# RoBeast_Current_Sense.net
KiCad netlist of a schematic drawn in Altium Designer
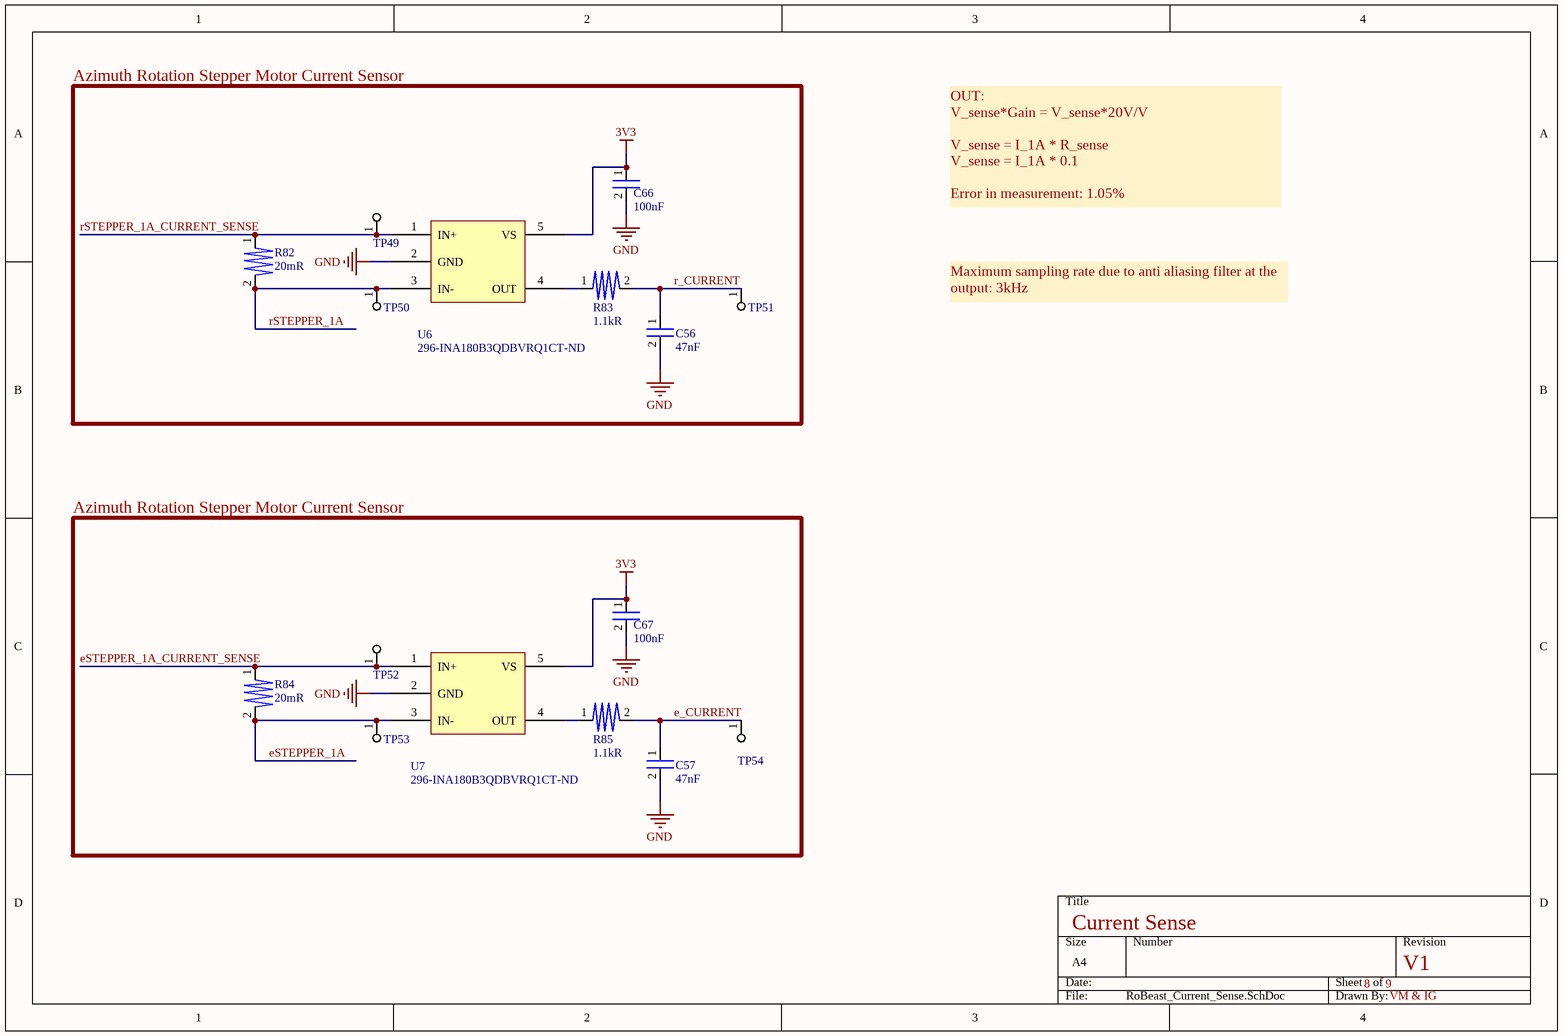
[diagram p0: RoBeast_Current_Sense.SchDoc]

(export (version "E")
  (design (tool "Eeschema 10.0.6"))
  (components
    (comp (ref "C56")
      (value "47nF")
      (footprint "0805")
      (fields
        (field (name "MANUFACTURER") "Samsung")
        (field (name "MANUFACTURER PART NUMBER") "CL21B473KBCNNNC")
      )
      (libsource (lib "RoBeast_Schematic_Library") (part "CL21B473KBCNNNC"))
    )
    (comp (ref "C57")
      (value "47nF")
      (footprint "0805")
      (fields
        (field (name "MANUFACTURER") "Samsung")
        (field (name "MANUFACTURER PART NUMBER") "CL21B473KBCNNNC")
      )
      (libsource (lib "RoBeast_Schematic_Library") (part "CL21B473KBCNNNC"))
    )
    (comp (ref "C66")
      (value "100nF")
      (footprint "0805")
      (fields
        (field (name "MANUFACTURER") "KEMET")
        (field (name "MANUFACTURER PART NUMBER") "C0805C104J5RACTU")
      )
      (libsource (lib "RoBeast_Schematic_Library") (part "C0805C104J5RAC7800"))
    )
    (comp (ref "C67")
      (value "100nF")
      (footprint "0805")
      (fields
        (field (name "MANUFACTURER") "KEMET")
        (field (name "MANUFACTURER PART NUMBER") "C0805C104J5RACTU")
      )
      (libsource (lib "RoBeast_Schematic_Library") (part "C0805C104J5RAC7800"))
    )
    (comp (ref "R82")
      (value "20mR")
      (footprint "0805")
      (description "Resistor Thick Film 0.02Ohm 0.5% 0.5W 2-Pin 0805 T/R")
      (fields
        (field (name "MANUFACTURER") "Panasonic")
        (field (name "MANUFACTURER PART NUMBER") "ERJ-6CWDR020V")
      )
      (libsource (lib "RoBeast_Schematic_Library") (part "ERJ-6CWDR020V"))
    )
    (comp (ref "R83")
      (value "1.1kR")
      (footprint "0805")
      (fields
        (field (name "MANUFACTURER") "Vishay Dale")
        (field (name "MANUFACTURER PART NUMBER") "RCS08051K10FKEA")
      )
      (libsource (lib "RoBeast_Schematic_Library") (part "RCS08051K10FKEA"))
    )
    (comp (ref "R84")
      (value "20mR")
      (footprint "0805")
      (description "Resistor Thick Film 0.02Ohm 0.5% 0.5W 2-Pin 0805 T/R")
      (fields
        (field (name "MANUFACTURER") "Panasonic")
        (field (name "MANUFACTURER PART NUMBER") "ERJ-6CWDR020V")
      )
      (libsource (lib "RoBeast_Schematic_Library") (part "ERJ-6CWDR020V"))
    )
    (comp (ref "R85")
      (value "1.1kR")
      (footprint "0805")
      (fields
        (field (name "MANUFACTURER") "Vishay Dale")
        (field (name "MANUFACTURER PART NUMBER") "RCS08051K10FKEA")
      )
      (libsource (lib "RoBeast_Schematic_Library") (part "RCS08051K10FKEA"))
    )
    (comp (ref "TP49")
      (value "Test Point")
      (footprint "RCWCTE")
      (description "Testing/Accessories")
      (fields (field (name "MANUFACTURER") "KOA Speer") (field (name "MANUFACTURER PART NUMBER") "RCWCTE"))
      (libsource (lib "RoBeast_Schematic_Library") (part "RCWCTE"))
    )
    (comp (ref "TP50")
      (value "Test Point")
      (footprint "RCWCTE")
      (description "Testing/Accessories")
      (fields (field (name "MANUFACTURER") "KOA Speer") (field (name "MANUFACTURER PART NUMBER") "RCWCTE"))
      (libsource (lib "RoBeast_Schematic_Library") (part "RCWCTE"))
    )
    (comp (ref "TP51")
      (value "Test Point")
      (footprint "RCWCTE")
      (description "Testing/Accessories")
      (fields (field (name "MANUFACTURER") "KOA Speer") (field (name "MANUFACTURER PART NUMBER") "RCWCTE"))
      (libsource (lib "RoBeast_Schematic_Library") (part "RCWCTE"))
    )
    (comp (ref "TP52")
      (value "Test Point")
      (footprint "RCWCTE")
      (description "Testing/Accessories")
      (fields (field (name "MANUFACTURER") "KOA Speer") (field (name "MANUFACTURER PART NUMBER") "RCWCTE"))
      (libsource (lib "RoBeast_Schematic_Library") (part "RCWCTE"))
    )
    (comp (ref "TP53")
      (value "Test Point")
      (footprint "RCWCTE")
      (description "Testing/Accessories")
      (fields (field (name "MANUFACTURER") "KOA Speer") (field (name "MANUFACTURER PART NUMBER") "RCWCTE"))
      (libsource (lib "RoBeast_Schematic_Library") (part "RCWCTE"))
    )
    (comp (ref "TP54")
      (value "Test Point")
      (footprint "RCWCTE")
      (description "Testing/Accessories")
      (fields (field (name "MANUFACTURER") "KOA Speer") (field (name "MANUFACTURER PART NUMBER") "RCWCTE"))
      (libsource (lib "RoBeast_Schematic_Library") (part "RCWCTE"))
    )
    (comp (ref "U6")
      (value "Current Sensor, Gain 100V/V")
      (footprint "INA180B3QDBVRQ1")
      (description "Operational Amplifier, 1 Func, 500uV Offset-Max, PDSO5")
      (fields
        (field (name "MANUFACTURER") "Texas Instruments")
        (field (name "MANUFACTURER PART NUMBER") "INA180B3QDBVRQ1")
        (field (name "SUPPLIER PART NUMBER 1") "296-INA180B3QDBVRQ1CT-ND")
      )
      (libsource (lib "RoBeast_Schematic_Library") (part "INA180B3QDBVRQ1"))
    )
    (comp (ref "U7")
      (value "Current Sensor, Gain 100V/V")
      (footprint "INA180B3QDBVRQ1")
      (description "Operational Amplifier, 1 Func, 500uV Offset-Max, PDSO5")
      (fields
        (field (name "MANUFACTURER") "Texas Instruments")
        (field (name "MANUFACTURER PART NUMBER") "INA180B3QDBVRQ1")
        (field (name "SUPPLIER PART NUMBER 1") "296-INA180B3QDBVRQ1CT-ND")
      )
      (libsource (lib "RoBeast_Schematic_Library") (part "INA180B3QDBVRQ1"))
    )
  )
  (nets
    (net (code "1") (name "/eSTEPPER_1A") (class "Default")
      (node (ref "R84") (pin "2") (pinfunction "2_2") (pintype "passive"))
      (node (ref "TP53") (pin "1") (pinfunction "1_1") (pintype "passive"))
      (node (ref "U7") (pin "3") (pinfunction "IN-_3") (pintype "passive"))
    )
    (net (code "2") (name "/eSTEPPER_1A_CURRENT_SENSE") (class "Default")
      (node (ref "R84") (pin "1") (pinfunction "1_1") (pintype "passive"))
      (node (ref "TP52") (pin "1") (pinfunction "1_1") (pintype "passive"))
      (node (ref "U7") (pin "1") (pinfunction "IN+_1") (pintype "passive"))
    )
    (net (code "3") (name "/e_CURRENT") (class "Default")
      (node (ref "C57") (pin "1") (pinfunction "1_1") (pintype "passive"))
      (node (ref "R85") (pin "2") (pinfunction "2_2") (pintype "passive"))
      (node (ref "TP54") (pin "1") (pinfunction "1_1") (pintype "passive"))
    )
    (net (code "4") (name "/rSTEPPER_1A") (class "Default")
      (node (ref "R82") (pin "2") (pinfunction "2_2") (pintype "passive"))
      (node (ref "TP50") (pin "1") (pinfunction "1_1") (pintype "passive"))
      (node (ref "U6") (pin "3") (pinfunction "IN-_3") (pintype "passive"))
    )
    (net (code "5") (name "/rSTEPPER_1A_CURRENT_SENSE") (class "Default")
      (node (ref "R82") (pin "1") (pinfunction "1_1") (pintype "passive"))
      (node (ref "TP49") (pin "1") (pinfunction "1_1") (pintype "passive"))
      (node (ref "U6") (pin "1") (pinfunction "IN+_1") (pintype "passive"))
    )
    (net (code "6") (name "/r_CURRENT") (class "Default")
      (node (ref "C56") (pin "1") (pinfunction "1_1") (pintype "passive"))
      (node (ref "R83") (pin "2") (pinfunction "2_2") (pintype "passive"))
      (node (ref "TP51") (pin "1") (pinfunction "1_1") (pintype "passive"))
    )
    (net (code "7") (name "3V3") (class "Default")
      (node (ref "C66") (pin "1") (pinfunction "1_1") (pintype "passive"))
      (node (ref "C67") (pin "1") (pinfunction "1_1") (pintype "passive"))
      (node (ref "U6") (pin "5") (pinfunction "VS_5") (pintype "passive"))
      (node (ref "U7") (pin "5") (pinfunction "VS_5") (pintype "passive"))
    )
    (net (code "8") (name "GND") (class "Default")
      (node (ref "C56") (pin "2") (pinfunction "2_2") (pintype "passive"))
      (node (ref "C57") (pin "2") (pinfunction "2_2") (pintype "passive"))
      (node (ref "C66") (pin "2") (pinfunction "2_2") (pintype "passive"))
      (node (ref "C67") (pin "2") (pinfunction "2_2") (pintype "passive"))
      (node (ref "U6") (pin "2") (pinfunction "GND_2") (pintype "passive"))
      (node (ref "U7") (pin "2") (pinfunction "GND_2") (pintype "passive"))
    )
    (net (code "9") (name "Net-(U6-OUT)") (class "Default")
      (node (ref "R83") (pin "1") (pinfunction "1_1") (pintype "passive"))
      (node (ref "U6") (pin "4") (pinfunction "OUT_4") (pintype "passive"))
    )
    (net (code "10") (name "Net-(U7-OUT)") (class "Default")
      (node (ref "R85") (pin "1") (pinfunction "1_1") (pintype "passive"))
      (node (ref "U7") (pin "4") (pinfunction "OUT_4") (pintype "passive"))
    )
  )
)
